# DIY-USB_Led_Controller.net
KiCad netlist of a schematic drawn in Altium Designer
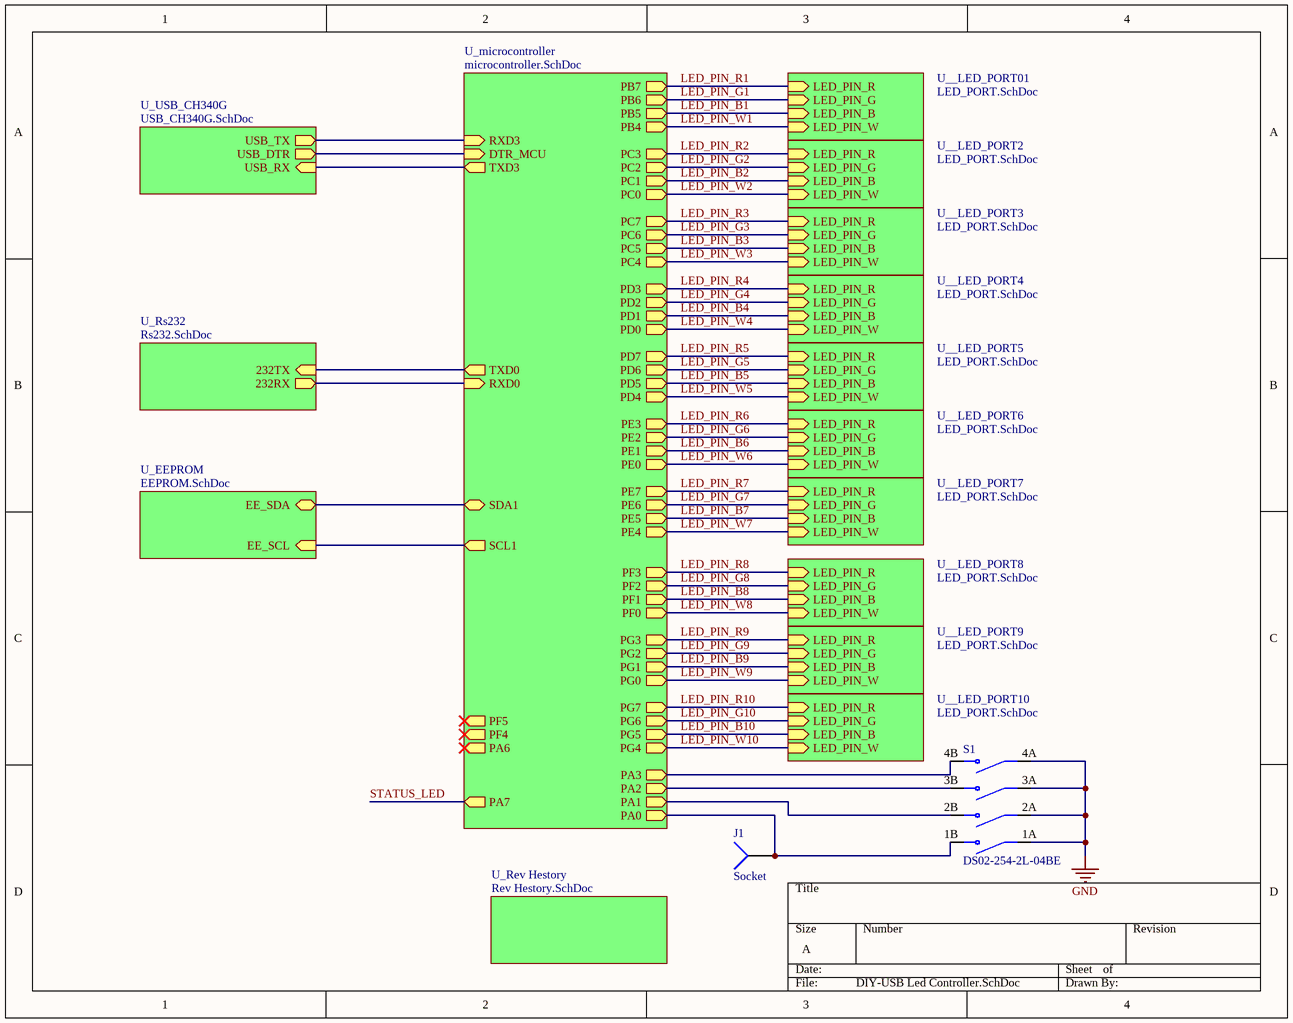
[diagram p0: DIY-USB Led Controller.SchDoc]

(export (version "E")
  (design (tool "Eeschema 10.0.6"))
  (components
    (comp (ref "J1")
      (value "Socket")
      (footprint "PIN1")
      (fields (field (name "PUBLISHER") "Altium Limited"))
      (libsource (lib "Miscellaneous Connectors") (part "Socket"))
    )
    (comp (ref "S1")
      (value "DS02-254-2L-04BE")
      (footprint "SW_DS02-254-2L-04BE")
      (description "Dip Switch SPST 4 Position Through Hole, Right Angle Piano Actuator 25mA 24VDC")
      (libsource (lib "DS02-254-2L-04BE") (part "DS02-254-2L-04BE"))
    )
  )
  (nets
    (net (code "43") (name "/PA0") (class "Default")
      (node (ref "J1") (pin "1") (pinfunction "1_1") (pintype "passive"))
      (node (ref "S1") (pin "1B") (pinfunction "NO1_1B") (pintype "passive"))
    )
    (net (code "44") (name "/PA1") (class "Default")
      (node (ref "S1") (pin "2B") (pinfunction "NO2_2B") (pintype "passive"))
    )
    (net (code "45") (name "/PA2") (class "Default")
      (node (ref "S1") (pin "3B") (pinfunction "NO3_3B") (pintype "passive"))
    )
    (net (code "46") (name "/PA3") (class "Default")
      (node (ref "S1") (pin "4B") (pinfunction "NO4_4B") (pintype "passive"))
    )
    (net (code "56") (name "GND") (class "Default")
      (node (ref "S1") (pin "1A") (pinfunction "COM1_1A") (pintype "passive"))
      (node (ref "S1") (pin "2A") (pinfunction "COM2_2A") (pintype "passive"))
      (node (ref "S1") (pin "3A") (pinfunction "COM3_3A") (pintype "passive"))
      (node (ref "S1") (pin "4A") (pinfunction "COM4_4A") (pintype "passive"))
    )
  )
)
